# master.net
KiCad netlist of a schematic drawn in EAGLE
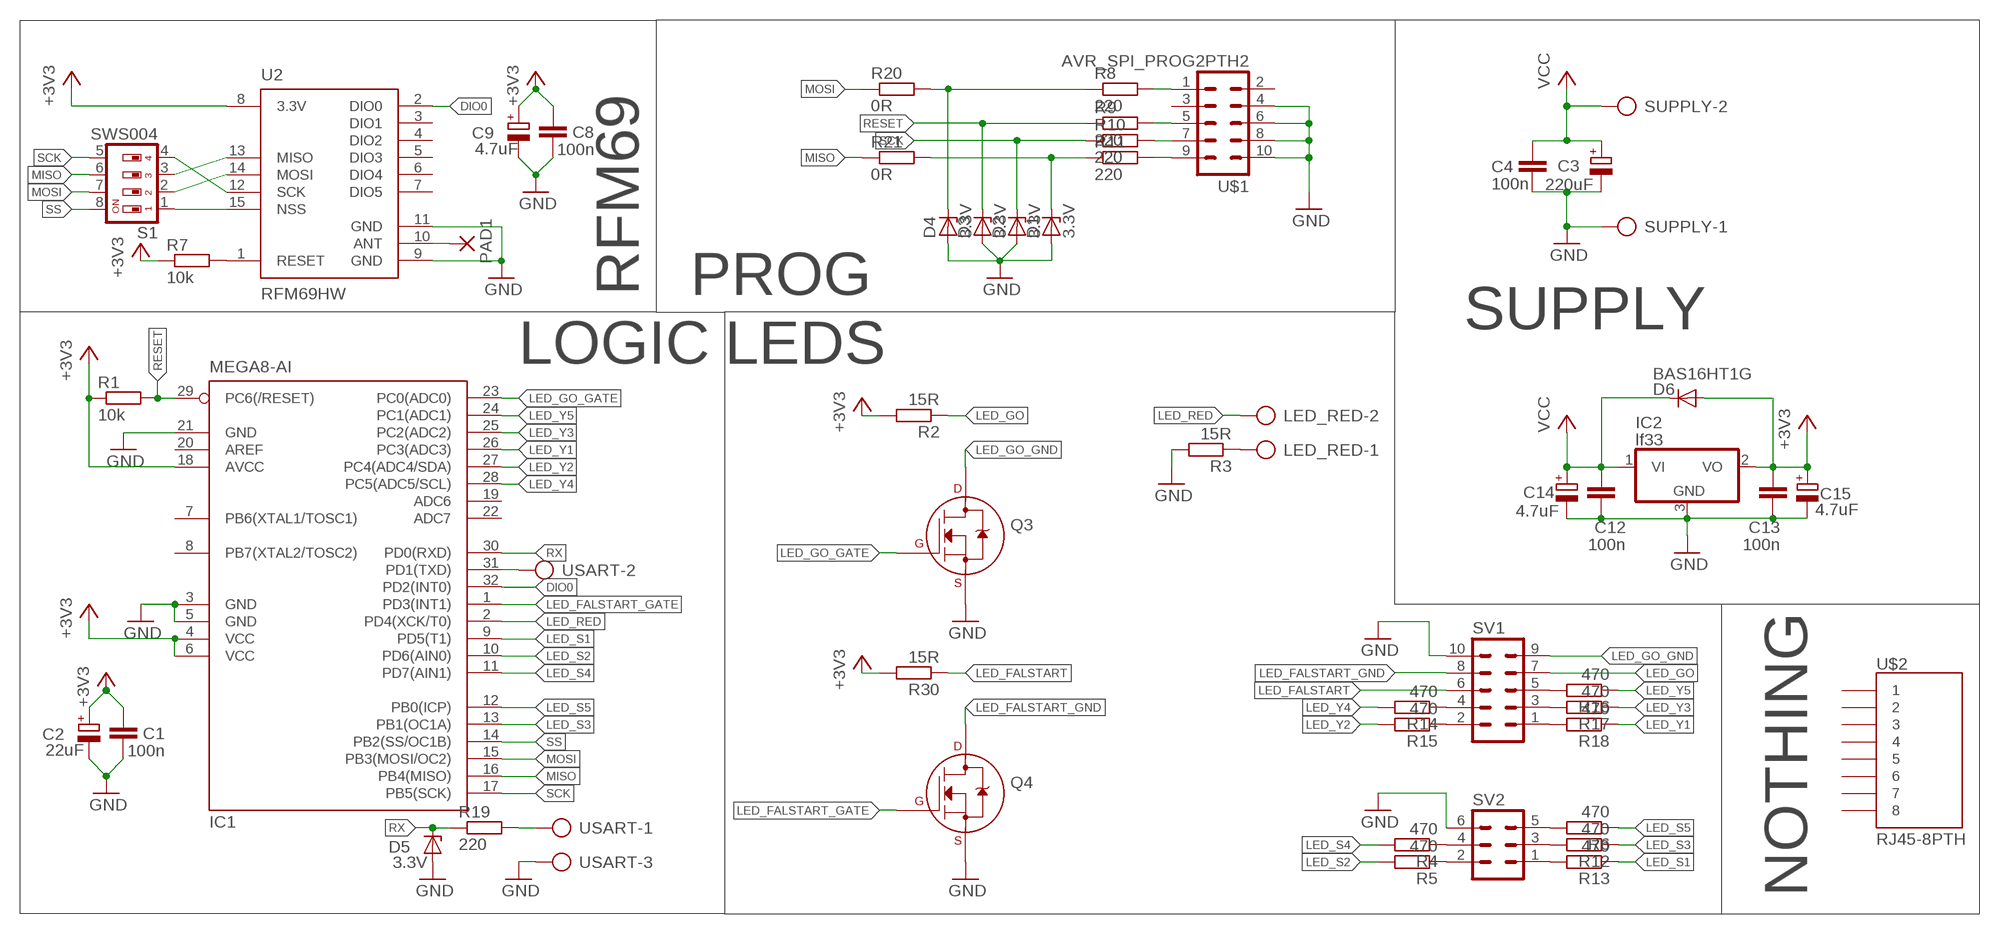
[diagram p0: schematic, sheet 1]

(export (version "E")
  (design (tool "Eeschema 10.0.6"))
  (components
    (comp (ref "C1")
      (value "100n")
      (footprint "eagle-import:C0805")
      (libsource (lib "eagle-import") (part "C-EUC0805"))
    )
    (comp (ref "C2")
      (value "22uF")
      (footprint "eagle-import:E2-5")
      (libsource (lib "eagle-import") (part "CPOL-EUE2-5"))
    )
    (comp (ref "C3")
      (value "220uF")
      (footprint "eagle-import:E2-5")
      (libsource (lib "eagle-import") (part "CPOL-EUE2-5"))
    )
    (comp (ref "C4")
      (value "100n")
      (footprint "eagle-import:C0805")
      (libsource (lib "eagle-import") (part "C-EUC0805"))
    )
    (comp (ref "C8")
      (value "100n")
      (footprint "eagle-import:C0805")
      (libsource (lib "eagle-import") (part "C-EUC0805"))
    )
    (comp (ref "C9")
      (value "4.7uF")
      (footprint "eagle-import:E2-5")
      (libsource (lib "eagle-import") (part "CPOL-EUE2-5"))
    )
    (comp (ref "C12")
      (value "100n")
      (footprint "eagle-import:C0805")
      (libsource (lib "eagle-import") (part "C-EUC0805"))
    )
    (comp (ref "C13")
      (value "100n")
      (footprint "eagle-import:C0805")
      (libsource (lib "eagle-import") (part "C-EUC0805"))
    )
    (comp (ref "C14")
      (value "4.7uF")
      (footprint "eagle-import:E2-5")
      (libsource (lib "eagle-import") (part "CPOL-EUE2-5"))
    )
    (comp (ref "C15")
      (value "4.7uF")
      (footprint "eagle-import:E2-5")
      (libsource (lib "eagle-import") (part "CPOL-EUE2-5"))
    )
    (comp (ref "D1")
      (value "3.3V")
      (footprint "eagle-import:SOD80C")
      (libsource (lib "eagle-import") (part "ZENER-DIODESOD80C"))
    )
    (comp (ref "D2")
      (value "3.3V")
      (footprint "eagle-import:SOD80C")
      (libsource (lib "eagle-import") (part "ZENER-DIODESOD80C"))
    )
    (comp (ref "D3")
      (value "3.3V")
      (footprint "eagle-import:SOD80C")
      (libsource (lib "eagle-import") (part "ZENER-DIODESOD80C"))
    )
    (comp (ref "D4")
      (value "3.3V")
      (footprint "eagle-import:SOD80C")
      (libsource (lib "eagle-import") (part "ZENER-DIODESOD80C"))
    )
    (comp (ref "D5")
      (value "3.3V")
      (footprint "eagle-import:SOD80C")
      (libsource (lib "eagle-import") (part "ZENER-DIODESOD80C"))
    )
    (comp (ref "D6")
      (value "BAS16HT1G")
      (footprint "eagle-import:DO214AC")
      (libsource (lib "eagle-import") (part "DIODE-DO214AC"))
    )
    (comp (ref "IC1")
      (value "MEGA8-AI")
      (footprint "eagle-import:TQFP32-08")
      (fields (field (name "MPN") "ATMEGA8-16AU"))
      (libsource (lib "eagle-import") (part "MEGA8-AI"))
    )
    (comp (ref "IC2")
      (value "lf33")
      (footprint "eagle-import:TO252")
      (libsource (lib "eagle-import") (part "78DT06"))
    )
    (comp (ref "LED_RED")
      (value "AK500/2")
      (footprint "eagle-import:AK500_2")
      (libsource (lib "eagle-import") (part "AK500/2"))
    )
    (comp (ref "PAD1")
      (value "WIREPADSMD5-2,5")
      (footprint "eagle-import:5-2,5")
      (libsource (lib "eagle-import") (part "WIREPADSMD5-2,5"))
    )
    (comp (ref "Q3")
      (value "2N7000_SOT23")
      (footprint "eagle-import:SOT-23")
      (libsource (lib "eagle-import") (part "2N700_SOT230"))
    )
    (comp (ref "Q4")
      (value "2N7000_SOT23")
      (footprint "eagle-import:SOT-23")
      (libsource (lib "eagle-import") (part "2N700_SOT230"))
    )
    (comp (ref "R1")
      (value "10k")
      (footprint "eagle-import:R0805")
      (libsource (lib "eagle-import") (part "R-EU_R0805"))
    )
    (comp (ref "R2")
      (value "15R")
      (footprint "eagle-import:R0805")
      (libsource (lib "eagle-import") (part "R-EU_R0805"))
    )
    (comp (ref "R3")
      (value "15R")
      (footprint "eagle-import:R0805")
      (libsource (lib "eagle-import") (part "R-EU_R0805"))
    )
    (comp (ref "R4")
      (value "470")
      (footprint "eagle-import:R0805")
      (libsource (lib "eagle-import") (part "R-EU_R0805"))
    )
    (comp (ref "R5")
      (value "470")
      (footprint "eagle-import:R0805")
      (libsource (lib "eagle-import") (part "R-EU_R0805"))
    )
    (comp (ref "R6")
      (value "470")
      (footprint "eagle-import:R0805")
      (libsource (lib "eagle-import") (part "R-EU_R0805"))
    )
    (comp (ref "R7")
      (value "10k")
      (footprint "eagle-import:R0805")
      (libsource (lib "eagle-import") (part "R-EU_R0805"))
    )
    (comp (ref "R8")
      (value "220")
      (footprint "eagle-import:R0805")
      (libsource (lib "eagle-import") (part "R-EU_R0805"))
    )
    (comp (ref "R9")
      (value "220")
      (footprint "eagle-import:R0805")
      (libsource (lib "eagle-import") (part "R-EU_R0805"))
    )
    (comp (ref "R10")
      (value "220")
      (footprint "eagle-import:R0805")
      (libsource (lib "eagle-import") (part "R-EU_R0805"))
    )
    (comp (ref "R11")
      (value "220")
      (footprint "eagle-import:R0805")
      (libsource (lib "eagle-import") (part "R-EU_R0805"))
    )
    (comp (ref "R12")
      (value "470")
      (footprint "eagle-import:R0805")
      (libsource (lib "eagle-import") (part "R-EU_R0805"))
    )
    (comp (ref "R13")
      (value "470")
      (footprint "eagle-import:R0805")
      (libsource (lib "eagle-import") (part "R-EU_R0805"))
    )
    (comp (ref "R14")
      (value "470")
      (footprint "eagle-import:R0805")
      (libsource (lib "eagle-import") (part "R-EU_R0805"))
    )
    (comp (ref "R15")
      (value "470")
      (footprint "eagle-import:R0805")
      (libsource (lib "eagle-import") (part "R-EU_R0805"))
    )
    (comp (ref "R16")
      (value "470")
      (footprint "eagle-import:R0805")
      (libsource (lib "eagle-import") (part "R-EU_R0805"))
    )
    (comp (ref "R17")
      (value "470")
      (footprint "eagle-import:R0805")
      (libsource (lib "eagle-import") (part "R-EU_R0805"))
    )
    (comp (ref "R18")
      (value "470")
      (footprint "eagle-import:R0805")
      (libsource (lib "eagle-import") (part "R-EU_R0805"))
    )
    (comp (ref "R19")
      (value "220")
      (footprint "eagle-import:R0805")
      (libsource (lib "eagle-import") (part "R-EU_R0805"))
    )
    (comp (ref "R20")
      (value "0R")
      (footprint "eagle-import:R1206")
      (libsource (lib "eagle-import") (part "R-EU_R1206"))
    )
    (comp (ref "R21")
      (value "0R")
      (footprint "eagle-import:R1206")
      (libsource (lib "eagle-import") (part "R-EU_R1206"))
    )
    (comp (ref "R30")
      (value "15R")
      (footprint "eagle-import:R0805")
      (libsource (lib "eagle-import") (part "R-EU_R0805"))
    )
    (comp (ref "S1")
      (value "SWS004")
      (footprint "eagle-import:SMS-004")
      (libsource (lib "eagle-import") (part "SWS004"))
    )
    (comp (ref "SUPPLY")
      (value "AK500/2")
      (footprint "eagle-import:AK500_2")
      (libsource (lib "eagle-import") (part "AK500/2"))
    )
    (comp (ref "SV1")
      (value "ML10")
      (footprint "eagle-import:ML10")
      (libsource (lib "eagle-import") (part "ML10"))
    )
    (comp (ref "SV2")
      (value "ML6")
      (footprint "eagle-import:ML6")
      (libsource (lib "eagle-import") (part "ML6"))
    )
    (comp (ref "U$1")
      (value "AVR_SPI_PROG2PTH2")
      (footprint "eagle-import:ML10L")
      (libsource (lib "eagle-import") (part "ML10L"))
    )
    (comp (ref "U$2")
      (value "RJ45-8PTH")
      (footprint "eagle-import:RJ45-8")
      (libsource (lib "eagle-import") (part "RJ45-8PTH"))
    )
    (comp (ref "U2")
      (value "RFM69HW")
      (footprint "eagle-import:RFM69W-XXXS2")
      (libsource (lib "eagle-import") (part "RFM69HW"))
    )
    (comp (ref "USART")
      (value "AK500/3")
      (footprint "eagle-import:AK500_3")
      (libsource (lib "eagle-import") (part "AK500/3"))
    )
  )
  (nets
    (net (code "1") (name "+3V3") (class "Default")
      (node (ref "C1") (pin "1") (pinfunction "1_1") (pintype "passive"))
      (node (ref "C13") (pin "1") (pinfunction "1_1") (pintype "passive"))
      (node (ref "C15") (pin "+") (pinfunction "+_+") (pintype "passive"))
      (node (ref "C2") (pin "+") (pinfunction "+_+") (pintype "passive"))
      (node (ref "C8") (pin "1") (pinfunction "1_1") (pintype "passive"))
      (node (ref "C9") (pin "+") (pinfunction "+_+") (pintype "passive"))
      (node (ref "D6") (pin "A") (pinfunction "A_A") (pintype "passive"))
      (node (ref "IC1") (pin "18") (pinfunction "AVCC_18") (pintype "power_in"))
      (node (ref "IC1") (pin "4") (pinfunction "VCC_4") (pintype "power_in"))
      (node (ref "IC1") (pin "6") (pinfunction "VCC_6") (pintype "power_in"))
      (node (ref "IC2") (pin "2") (pinfunction "VO_2") (pintype "passive"))
      (node (ref "R1") (pin "1") (pinfunction "1_1") (pintype "passive"))
      (node (ref "R2") (pin "2") (pinfunction "2_2") (pintype "passive"))
      (node (ref "R30") (pin "2") (pinfunction "2_2") (pintype "passive"))
      (node (ref "R7") (pin "1") (pinfunction "1_1") (pintype "passive"))
      (node (ref "U2") (pin "8") (pinfunction "3.3V_8") (pintype "power_in"))
    )
    (net (code "2") (name "DIO0") (class "Default")
      (node (ref "IC1") (pin "32") (pinfunction "PD2(INT0)_32") (pintype "bidirectional"))
      (node (ref "U2") (pin "2") (pinfunction "DIO0_2") (pintype "bidirectional"))
    )
    (net (code "3") (name "GND") (class "Default")
      (node (ref "C1") (pin "2") (pinfunction "2_2") (pintype "passive"))
      (node (ref "C12") (pin "2") (pinfunction "2_2") (pintype "passive"))
      (node (ref "C13") (pin "2") (pinfunction "2_2") (pintype "passive"))
      (node (ref "C14") (pin "-") (pinfunction "-_-") (pintype "passive"))
      (node (ref "C15") (pin "-") (pinfunction "-_-") (pintype "passive"))
      (node (ref "C2") (pin "-") (pinfunction "-_-") (pintype "passive"))
      (node (ref "C3") (pin "-") (pinfunction "-_-") (pintype "passive"))
      (node (ref "C4") (pin "2") (pinfunction "2_2") (pintype "passive"))
      (node (ref "C8") (pin "2") (pinfunction "2_2") (pintype "passive"))
      (node (ref "C9") (pin "-") (pinfunction "-_-") (pintype "passive"))
      (node (ref "D1") (pin "A") (pinfunction "A_A") (pintype "passive"))
      (node (ref "D2") (pin "A") (pinfunction "A_A") (pintype "passive"))
      (node (ref "D3") (pin "A") (pinfunction "A_A") (pintype "passive"))
      (node (ref "D4") (pin "A") (pinfunction "A_A") (pintype "passive"))
      (node (ref "D5") (pin "A") (pinfunction "A_A") (pintype "passive"))
      (node (ref "IC1") (pin "21") (pinfunction "GND_21") (pintype "power_in"))
      (node (ref "IC1") (pin "3") (pinfunction "GND_3") (pintype "power_in"))
      (node (ref "IC1") (pin "5") (pinfunction "GND_5") (pintype "power_in"))
      (node (ref "IC2") (pin "3") (pinfunction "GND_3") (pintype "passive"))
      (node (ref "Q3") (pin "2") (pinfunction "S_2") (pintype "bidirectional"))
      (node (ref "Q4") (pin "2") (pinfunction "S_2") (pintype "bidirectional"))
      (node (ref "R3") (pin "2") (pinfunction "2_2") (pintype "passive"))
      (node (ref "SUPPLY") (pin "1") (pinfunction "KL_1") (pintype "passive"))
      (node (ref "SV1") (pin "10") (pinfunction "10_10") (pintype "passive"))
      (node (ref "SV2") (pin "6") (pinfunction "6_6") (pintype "passive"))
      (node (ref "U$1") (pin "10") (pinfunction "10_10") (pintype "passive"))
      (node (ref "U$1") (pin "4") (pinfunction "4_4") (pintype "passive"))
      (node (ref "U$1") (pin "6") (pinfunction "6_6") (pintype "passive"))
      (node (ref "U$1") (pin "8") (pinfunction "8_8") (pintype "passive"))
      (node (ref "U2") (pin "11") (pinfunction "GND_11") (pintype "power_in"))
      (node (ref "U2") (pin "9") (pinfunction "GND_9") (pintype "power_in"))
      (node (ref "USART") (pin "3") (pinfunction "KL_3") (pintype "passive"))
    )
    (net (code "4") (name "LED_FALSTART") (class "Default")
      (node (ref "R30") (pin "1") (pinfunction "1_1") (pintype "passive"))
      (node (ref "SV1") (pin "6") (pinfunction "6_6") (pintype "passive"))
    )
    (net (code "5") (name "LED_FALSTART_GATE") (class "Default")
      (node (ref "IC1") (pin "1") (pinfunction "PD3(INT1)_1") (pintype "bidirectional"))
      (node (ref "Q4") (pin "1") (pinfunction "G_1") (pintype "tri_state"))
    )
    (net (code "6") (name "LED_FALSTART_GND") (class "Default")
      (node (ref "Q4") (pin "3") (pinfunction "D_3") (pintype "bidirectional"))
      (node (ref "SV1") (pin "8") (pinfunction "8_8") (pintype "passive"))
    )
    (net (code "7") (name "LED_GO") (class "Default")
      (node (ref "R2") (pin "1") (pinfunction "1_1") (pintype "passive"))
      (node (ref "SV1") (pin "7") (pinfunction "7_7") (pintype "passive"))
    )
    (net (code "8") (name "LED_GO_GATE") (class "Default")
      (node (ref "IC1") (pin "23") (pinfunction "PC0(ADC0)_23") (pintype "bidirectional"))
      (node (ref "Q3") (pin "1") (pinfunction "G_1") (pintype "tri_state"))
    )
    (net (code "9") (name "LED_GO_GND") (class "Default")
      (node (ref "Q3") (pin "3") (pinfunction "D_3") (pintype "bidirectional"))
      (node (ref "SV1") (pin "9") (pinfunction "9_9") (pintype "passive"))
    )
    (net (code "10") (name "LED_RED") (class "Default")
      (node (ref "IC1") (pin "2") (pinfunction "PD4(XCK/T0)_2") (pintype "bidirectional"))
      (node (ref "LED_RED") (pin "2") (pinfunction "KL_2") (pintype "passive"))
    )
    (net (code "11") (name "LED_S1") (class "Default")
      (node (ref "IC1") (pin "9") (pinfunction "PD5(T1)_9") (pintype "bidirectional"))
      (node (ref "R13") (pin "1") (pinfunction "1_1") (pintype "passive"))
    )
    (net (code "12") (name "LED_S2") (class "Default")
      (node (ref "IC1") (pin "10") (pinfunction "PD6(AIN0)_10") (pintype "bidirectional"))
      (node (ref "R5") (pin "2") (pinfunction "2_2") (pintype "passive"))
    )
    (net (code "13") (name "LED_S3") (class "Default")
      (node (ref "IC1") (pin "13") (pinfunction "PB1(OC1A)_13") (pintype "bidirectional"))
      (node (ref "R12") (pin "1") (pinfunction "1_1") (pintype "passive"))
    )
    (net (code "14") (name "LED_S4") (class "Default")
      (node (ref "IC1") (pin "11") (pinfunction "PD7(AIN1)_11") (pintype "bidirectional"))
      (node (ref "R4") (pin "2") (pinfunction "2_2") (pintype "passive"))
    )
    (net (code "15") (name "LED_S5") (class "Default")
      (node (ref "IC1") (pin "12") (pinfunction "PB0(ICP)_12") (pintype "bidirectional"))
      (node (ref "R6") (pin "1") (pinfunction "1_1") (pintype "passive"))
    )
    (net (code "16") (name "LED_Y1") (class "Default")
      (node (ref "IC1") (pin "26") (pinfunction "PC3(ADC3)_26") (pintype "bidirectional"))
      (node (ref "R18") (pin "1") (pinfunction "1_1") (pintype "passive"))
    )
    (net (code "17") (name "LED_Y2") (class "Default")
      (node (ref "IC1") (pin "27") (pinfunction "PC4(ADC4/SDA)_27") (pintype "bidirectional"))
      (node (ref "R15") (pin "2") (pinfunction "2_2") (pintype "passive"))
    )
    (net (code "18") (name "LED_Y3") (class "Default")
      (node (ref "IC1") (pin "25") (pinfunction "PC2(ADC2)_25") (pintype "bidirectional"))
      (node (ref "R17") (pin "1") (pinfunction "1_1") (pintype "passive"))
    )
    (net (code "19") (name "LED_Y4") (class "Default")
      (node (ref "IC1") (pin "28") (pinfunction "PC5(ADC5/SCL)_28") (pintype "bidirectional"))
      (node (ref "R14") (pin "2") (pinfunction "2_2") (pintype "passive"))
    )
    (net (code "20") (name "LED_Y5") (class "Default")
      (node (ref "IC1") (pin "24") (pinfunction "PC1(ADC1)_24") (pintype "bidirectional"))
      (node (ref "R16") (pin "1") (pinfunction "1_1") (pintype "passive"))
    )
    (net (code "21") (name "MISO") (class "Default")
      (node (ref "IC1") (pin "16") (pinfunction "PB4(MISO)_16") (pintype "bidirectional"))
      (node (ref "R21") (pin "1") (pinfunction "1_1") (pintype "passive"))
      (node (ref "S1") (pin "6") (pinfunction "6_6") (pintype "passive"))
    )
    (net (code "22") (name "MOSI") (class "Default")
      (node (ref "IC1") (pin "15") (pinfunction "PB3(MOSI/OC2)_15") (pintype "bidirectional"))
      (node (ref "R20") (pin "1") (pinfunction "1_1") (pintype "passive"))
      (node (ref "S1") (pin "7") (pinfunction "7_7") (pintype "passive"))
    )
    (net (code "23") (name "Net-(D1-PadC)") (class "Default")
      (node (ref "D1") (pin "C") (pinfunction "C_C") (pintype "passive"))
      (node (ref "R11") (pin "1") (pinfunction "1_1") (pintype "passive"))
      (node (ref "R21") (pin "2") (pinfunction "2_2") (pintype "passive"))
    )
    (net (code "24") (name "Net-(D4-PadC)") (class "Default")
      (node (ref "D4") (pin "C") (pinfunction "C_C") (pintype "passive"))
      (node (ref "R20") (pin "2") (pinfunction "2_2") (pintype "passive"))
      (node (ref "R8") (pin "1") (pinfunction "1_1") (pintype "passive"))
    )
    (net (code "25") (name "Net-(IC1-PD1(TXD))") (class "Default")
      (node (ref "IC1") (pin "31") (pinfunction "PD1(TXD)_31") (pintype "bidirectional"))
      (node (ref "USART") (pin "2") (pinfunction "KL_2") (pintype "passive"))
    )
    (net (code "26") (name "Net-(LED_REDA-KL)") (class "Default")
      (node (ref "LED_RED") (pin "1") (pinfunction "KL_1") (pintype "passive"))
      (node (ref "R3") (pin "1") (pinfunction "1_1") (pintype "passive"))
    )
    (net (code "27") (name "Net-(PAD1-P)") (class "Default")
      (node (ref "PAD1") (pin "1") (pinfunction "P_1") (pintype "passive"))
      (node (ref "U2") (pin "10") (pinfunction "ANT_10") (pintype "passive"))
    )
    (net (code "28") (name "Net-(R4-Pad1)") (class "Default")
      (node (ref "R4") (pin "1") (pinfunction "1_1") (pintype "passive"))
      (node (ref "SV2") (pin "4") (pinfunction "4_4") (pintype "passive"))
    )
    (net (code "29") (name "Net-(R5-Pad1)") (class "Default")
      (node (ref "R5") (pin "1") (pinfunction "1_1") (pintype "passive"))
      (node (ref "SV2") (pin "2") (pinfunction "2_2") (pintype "passive"))
    )
    (net (code "30") (name "Net-(R6-Pad2)") (class "Default")
      (node (ref "R6") (pin "2") (pinfunction "2_2") (pintype "passive"))
      (node (ref "SV2") (pin "5") (pinfunction "5_5") (pintype "passive"))
    )
    (net (code "31") (name "Net-(R8-Pad2)") (class "Default")
      (node (ref "R8") (pin "2") (pinfunction "2_2") (pintype "passive"))
      (node (ref "U$1") (pin "1") (pinfunction "1_1") (pintype "passive"))
    )
    (net (code "32") (name "Net-(R9-Pad2)") (class "Default")
      (node (ref "R9") (pin "2") (pinfunction "2_2") (pintype "passive"))
      (node (ref "U$1") (pin "5") (pinfunction "5_5") (pintype "passive"))
    )
    (net (code "33") (name "Net-(R10-Pad2)") (class "Default")
      (node (ref "R10") (pin "2") (pinfunction "2_2") (pintype "passive"))
      (node (ref "U$1") (pin "7") (pinfunction "7_7") (pintype "passive"))
    )
    (net (code "34") (name "Net-(R11-Pad2)") (class "Default")
      (node (ref "R11") (pin "2") (pinfunction "2_2") (pintype "passive"))
      (node (ref "U$1") (pin "9") (pinfunction "9_9") (pintype "passive"))
    )
    (net (code "35") (name "Net-(R12-Pad2)") (class "Default")
      (node (ref "R12") (pin "2") (pinfunction "2_2") (pintype "passive"))
      (node (ref "SV2") (pin "3") (pinfunction "3_3") (pintype "passive"))
    )
    (net (code "36") (name "Net-(R13-Pad2)") (class "Default")
      (node (ref "R13") (pin "2") (pinfunction "2_2") (pintype "passive"))
      (node (ref "SV2") (pin "1") (pinfunction "1_1") (pintype "passive"))
    )
    (net (code "37") (name "Net-(R14-Pad1)") (class "Default")
      (node (ref "R14") (pin "1") (pinfunction "1_1") (pintype "passive"))
      (node (ref "SV1") (pin "4") (pinfunction "4_4") (pintype "passive"))
    )
    (net (code "38") (name "Net-(R15-Pad1)") (class "Default")
      (node (ref "R15") (pin "1") (pinfunction "1_1") (pintype "passive"))
      (node (ref "SV1") (pin "2") (pinfunction "2_2") (pintype "passive"))
    )
    (net (code "39") (name "Net-(R16-Pad2)") (class "Default")
      (node (ref "R16") (pin "2") (pinfunction "2_2") (pintype "passive"))
      (node (ref "SV1") (pin "5") (pinfunction "5_5") (pintype "passive"))
    )
    (net (code "40") (name "Net-(R17-Pad2)") (class "Default")
      (node (ref "R17") (pin "2") (pinfunction "2_2") (pintype "passive"))
      (node (ref "SV1") (pin "3") (pinfunction "3_3") (pintype "passive"))
    )
    (net (code "41") (name "Net-(R18-Pad2)") (class "Default")
      (node (ref "R18") (pin "2") (pinfunction "2_2") (pintype "passive"))
      (node (ref "SV1") (pin "1") (pinfunction "1_1") (pintype "passive"))
    )
    (net (code "42") (name "Net-(U2-MISO)") (class "Default")
      (node (ref "S1") (pin "3") (pinfunction "3_3") (pintype "passive"))
      (node (ref "U2") (pin "13") (pinfunction "MISO_13") (pintype "bidirectional"))
    )
    (net (code "43") (name "Net-(U2-MOSI)") (class "Default")
      (node (ref "S1") (pin "2") (pinfunction "2_2") (pintype "passive"))
      (node (ref "U2") (pin "14") (pinfunction "MOSI_14") (pintype "input"))
    )
    (net (code "44") (name "Net-(U2-NSS)") (class "Default")
      (node (ref "S1") (pin "1") (pinfunction "1_1") (pintype "passive"))
      (node (ref "U2") (pin "15") (pinfunction "NSS_15") (pintype "input"))
    )
    (net (code "45") (name "Net-(U2-RESET)") (class "Default")
      (node (ref "R7") (pin "2") (pinfunction "2_2") (pintype "passive"))
      (node (ref "U2") (pin "1") (pinfunction "RESET_1") (pintype "input"))
    )
    (net (code "46") (name "Net-(U2-SCK)") (class "Default")
      (node (ref "S1") (pin "4") (pinfunction "4_4") (pintype "passive"))
      (node (ref "U2") (pin "12") (pinfunction "SCK_12") (pintype "input"))
    )
    (net (code "47") (name "Net-(USARTA-KL)") (class "Default")
      (node (ref "R19") (pin "2") (pinfunction "2_2") (pintype "passive"))
      (node (ref "USART") (pin "1") (pinfunction "KL_1") (pintype "passive"))
    )
    (net (code "48") (name "RESET") (class "Default")
      (node (ref "D3") (pin "C") (pinfunction "C_C") (pintype "passive"))
      (node (ref "IC1") (pin "29") (pinfunction "PC6(/RESET)_29") (pintype "bidirectional"))
      (node (ref "R1") (pin "2") (pinfunction "2_2") (pintype "passive"))
      (node (ref "R9") (pin "1") (pinfunction "1_1") (pintype "passive"))
    )
    (net (code "49") (name "RX") (class "Default")
      (node (ref "D5") (pin "C") (pinfunction "C_C") (pintype "passive"))
      (node (ref "IC1") (pin "30") (pinfunction "PD0(RXD)_30") (pintype "bidirectional"))
      (node (ref "R19") (pin "1") (pinfunction "1_1") (pintype "passive"))
    )
    (net (code "50") (name "SCK") (class "Default")
      (node (ref "D2") (pin "C") (pinfunction "C_C") (pintype "passive"))
      (node (ref "IC1") (pin "17") (pinfunction "PB5(SCK)_17") (pintype "bidirectional"))
      (node (ref "R10") (pin "1") (pinfunction "1_1") (pintype "passive"))
      (node (ref "S1") (pin "5") (pinfunction "5_5") (pintype "passive"))
    )
    (net (code "51") (name "SS") (class "Default")
      (node (ref "IC1") (pin "14") (pinfunction "PB2(SS/OC1B)_14") (pintype "bidirectional"))
      (node (ref "S1") (pin "8") (pinfunction "8_8") (pintype "passive"))
    )
    (net (code "52") (name "VCC") (class "Default")
      (node (ref "C12") (pin "1") (pinfunction "1_1") (pintype "passive"))
      (node (ref "C14") (pin "+") (pinfunction "+_+") (pintype "passive"))
      (node (ref "C3") (pin "+") (pinfunction "+_+") (pintype "passive"))
      (node (ref "C4") (pin "1") (pinfunction "1_1") (pintype "passive"))
      (node (ref "D6") (pin "C") (pinfunction "C_C") (pintype "passive"))
      (node (ref "IC2") (pin "1") (pinfunction "VI_1") (pintype "input"))
      (node (ref "SUPPLY") (pin "2") (pinfunction "KL_2") (pintype "passive"))
    )
    (net (code "53") (name "unconnected-(IC1-ADC6-Pad19)") (class "Default")
      (node (ref "IC1") (pin "19") (pinfunction "ADC6_19") (pintype "bidirectional"))
    )
    (net (code "54") (name "unconnected-(IC1-ADC7-Pad22)") (class "Default")
      (node (ref "IC1") (pin "22") (pinfunction "ADC7_22") (pintype "bidirectional"))
    )
    (net (code "55") (name "unconnected-(IC1-AREF-Pad20)") (class "Default")
      (node (ref "IC1") (pin "20") (pinfunction "AREF_20") (pintype "passive"))
    )
    (net (code "56") (name "unconnected-(IC1-PB6(XTAL1{slash}TOSC1)-Pad7)") (class "Default")
      (node (ref "IC1") (pin "7") (pinfunction "PB6(XTAL1/TOSC1)_7") (pintype "bidirectional"))
    )
    (net (code "57") (name "unconnected-(IC1-PB7(XTAL2{slash}TOSC2)-Pad8)") (class "Default")
      (node (ref "IC1") (pin "8") (pinfunction "PB7(XTAL2/TOSC2)_8") (pintype "bidirectional"))
    )
    (net (code "58") (name "unconnected-(U$1-Pad2)") (class "Default")
      (node (ref "U$1") (pin "2") (pinfunction "2_2") (pintype "passive"))
    )
    (net (code "59") (name "unconnected-(U$1-Pad3)") (class "Default")
      (node (ref "U$1") (pin "3") (pinfunction "3_3") (pintype "passive"))
    )
    (net (code "60") (name "unconnected-(U$2-Pad1)") (class "Default")
      (node (ref "U$2") (pin "1") (pinfunction "1_1") (pintype "bidirectional"))
    )
    (net (code "61") (name "unconnected-(U$2-Pad2)") (class "Default")
      (node (ref "U$2") (pin "2") (pinfunction "2_2") (pintype "bidirectional"))
    )
    (net (code "62") (name "unconnected-(U$2-Pad3)") (class "Default")
      (node (ref "U$2") (pin "3") (pinfunction "3_3") (pintype "bidirectional"))
    )
    (net (code "63") (name "unconnected-(U$2-Pad4)") (class "Default")
      (node (ref "U$2") (pin "4") (pinfunction "4_4") (pintype "bidirectional"))
    )
    (net (code "64") (name "unconnected-(U$2-Pad5)") (class "Default")
      (node (ref "U$2") (pin "5") (pinfunction "5_5") (pintype "bidirectional"))
    )
    (net (code "65") (name "unconnected-(U$2-Pad6)") (class "Default")
      (node (ref "U$2") (pin "6") (pinfunction "6_6") (pintype "bidirectional"))
    )
    (net (code "66") (name "unconnected-(U$2-Pad7)") (class "Default")
      (node (ref "U$2") (pin "7") (pinfunction "7_7") (pintype "bidirectional"))
    )
    (net (code "67") (name "unconnected-(U$2-Pad8)") (class "Default")
      (node (ref "U$2") (pin "8") (pinfunction "8_8") (pintype "bidirectional"))
    )
    (net (code "68") (name "unconnected-(U2-DIO1-Pad3)") (class "Default")
      (node (ref "U2") (pin "3") (pinfunction "DIO1_3") (pintype "bidirectional"))
    )
    (net (code "69") (name "unconnected-(U2-DIO2-Pad4)") (class "Default")
      (node (ref "U2") (pin "4") (pinfunction "DIO2_4") (pintype "bidirectional"))
    )
    (net (code "70") (name "unconnected-(U2-DIO3-Pad5)") (class "Default")
      (node (ref "U2") (pin "5") (pinfunction "DIO3_5") (pintype "bidirectional"))
    )
    (net (code "71") (name "unconnected-(U2-DIO4-Pad6)") (class "Default")
      (node (ref "U2") (pin "6") (pinfunction "DIO4_6") (pintype "bidirectional"))
    )
    (net (code "72") (name "unconnected-(U2-DIO5-Pad7)") (class "Default")
      (node (ref "U2") (pin "7") (pinfunction "DIO5_7") (pintype "bidirectional"))
    )
  )
)
